# connection.net
KiCad netlist of a schematic drawn in EAGLE
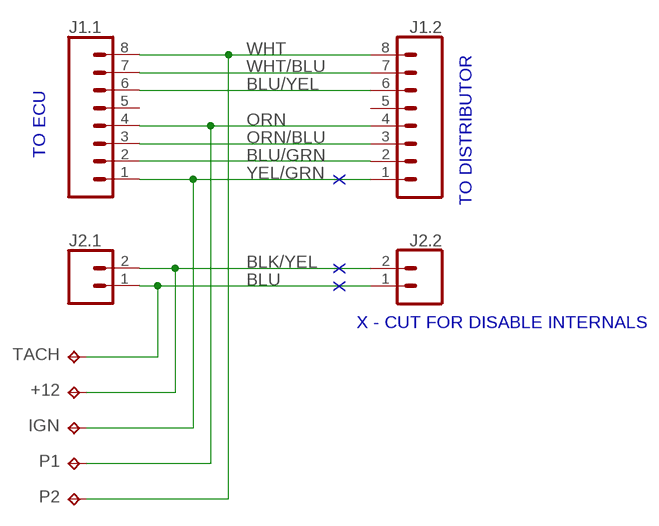
[diagram p0: schematic, sheet 1]

(export (version "E")
  (design (tool "Eeschema 10.0.6"))
  (components
    (comp (ref "+12")
      (value "TPB1,27")
      (footprint "eagle-import:B1,27")
      (libsource (lib "eagle-import") (part "TPB1,27"))
    )
    (comp (ref "IGN")
      (value "TPB1,27")
      (footprint "eagle-import:B1,27")
      (libsource (lib "eagle-import") (part "TPB1,27"))
    )
    (comp (ref "J1.1")
      (value "CONN_08\"")
      (footprint "eagle-import:1X08")
      (libsource (lib "eagle-import") (part "CONN_08{dblquote}"))
    )
    (comp (ref "J1.2")
      (value "CONN_08\"")
      (footprint "eagle-import:1X08")
      (libsource (lib "eagle-import") (part "CONN_08{dblquote}"))
    )
    (comp (ref "J2.1")
      (value "CONN_02")
      (footprint "eagle-import:1X02")
      (libsource (lib "eagle-import") (part "CONN_02"))
    )
    (comp (ref "J2.2")
      (value "CONN_02")
      (footprint "eagle-import:1X02")
      (libsource (lib "eagle-import") (part "CONN_02"))
    )
    (comp (ref "P1")
      (value "TPB1,27")
      (footprint "eagle-import:B1,27")
      (libsource (lib "eagle-import") (part "TPB1,27"))
    )
    (comp (ref "P2")
      (value "TPB1,27")
      (footprint "eagle-import:B1,27")
      (libsource (lib "eagle-import") (part "TPB1,27"))
    )
    (comp (ref "TACH")
      (value "TPB1,27")
      (footprint "eagle-import:B1,27")
      (libsource (lib "eagle-import") (part "TPB1,27"))
    )
  )
  (nets
    (net (code "1") (name "/BLK{slash}YEL") (class "Default")
      (node (ref "+12") (pin "TP") (pinfunction "TP_TP") (pintype "input"))
      (node (ref "J2.1") (pin "2") (pinfunction "2_2") (pintype "passive"))
      (node (ref "J2.2") (pin "2") (pinfunction "2_2") (pintype "passive"))
    )
    (net (code "2") (name "/BLU") (class "Default")
      (node (ref "J2.1") (pin "1") (pinfunction "1_1") (pintype "passive"))
      (node (ref "J2.2") (pin "1") (pinfunction "1_1") (pintype "passive"))
      (node (ref "TACH") (pin "TP") (pinfunction "TP_TP") (pintype "input"))
    )
    (net (code "3") (name "/BLU{slash}GRN") (class "Default")
      (node (ref "J1.1") (pin "2") (pinfunction "2_2") (pintype "passive"))
      (node (ref "J1.2") (pin "2") (pinfunction "2_2") (pintype "passive"))
    )
    (net (code "4") (name "/BLU{slash}YEL") (class "Default")
      (node (ref "J1.1") (pin "6") (pinfunction "6_6") (pintype "passive"))
      (node (ref "J1.2") (pin "6") (pinfunction "6_6") (pintype "passive"))
    )
    (net (code "5") (name "/ORN") (class "Default")
      (node (ref "J1.1") (pin "4") (pinfunction "4_4") (pintype "passive"))
      (node (ref "J1.2") (pin "4") (pinfunction "4_4") (pintype "passive"))
      (node (ref "P1") (pin "TP") (pinfunction "TP_TP") (pintype "input"))
    )
    (net (code "6") (name "/ORN{slash}BLU") (class "Default")
      (node (ref "J1.1") (pin "3") (pinfunction "3_3") (pintype "passive"))
      (node (ref "J1.2") (pin "3") (pinfunction "3_3") (pintype "passive"))
    )
    (net (code "7") (name "/WHT") (class "Default")
      (node (ref "J1.1") (pin "8") (pinfunction "8_8") (pintype "passive"))
      (node (ref "J1.2") (pin "8") (pinfunction "8_8") (pintype "passive"))
      (node (ref "P2") (pin "TP") (pinfunction "TP_TP") (pintype "input"))
    )
    (net (code "8") (name "/WHT{slash}BLU") (class "Default")
      (node (ref "J1.1") (pin "7") (pinfunction "7_7") (pintype "passive"))
      (node (ref "J1.2") (pin "7") (pinfunction "7_7") (pintype "passive"))
    )
    (net (code "9") (name "/YEL{slash}GRN") (class "Default")
      (node (ref "IGN") (pin "TP") (pinfunction "TP_TP") (pintype "input"))
      (node (ref "J1.1") (pin "1") (pinfunction "1_1") (pintype "passive"))
      (node (ref "J1.2") (pin "1") (pinfunction "1_1") (pintype "passive"))
    )
    (net (code "10") (name "unconnected-(J1.1-Pad5)") (class "Default")
      (node (ref "J1.1") (pin "5") (pinfunction "5_5") (pintype "passive"))
    )
    (net (code "11") (name "unconnected-(J1.2-Pad5)") (class "Default")
      (node (ref "J1.2") (pin "5") (pinfunction "5_5") (pintype "passive"))
    )
  )
)
